# instrumentacion.net
KiCad netlist of a schematic drawn in EAGLE
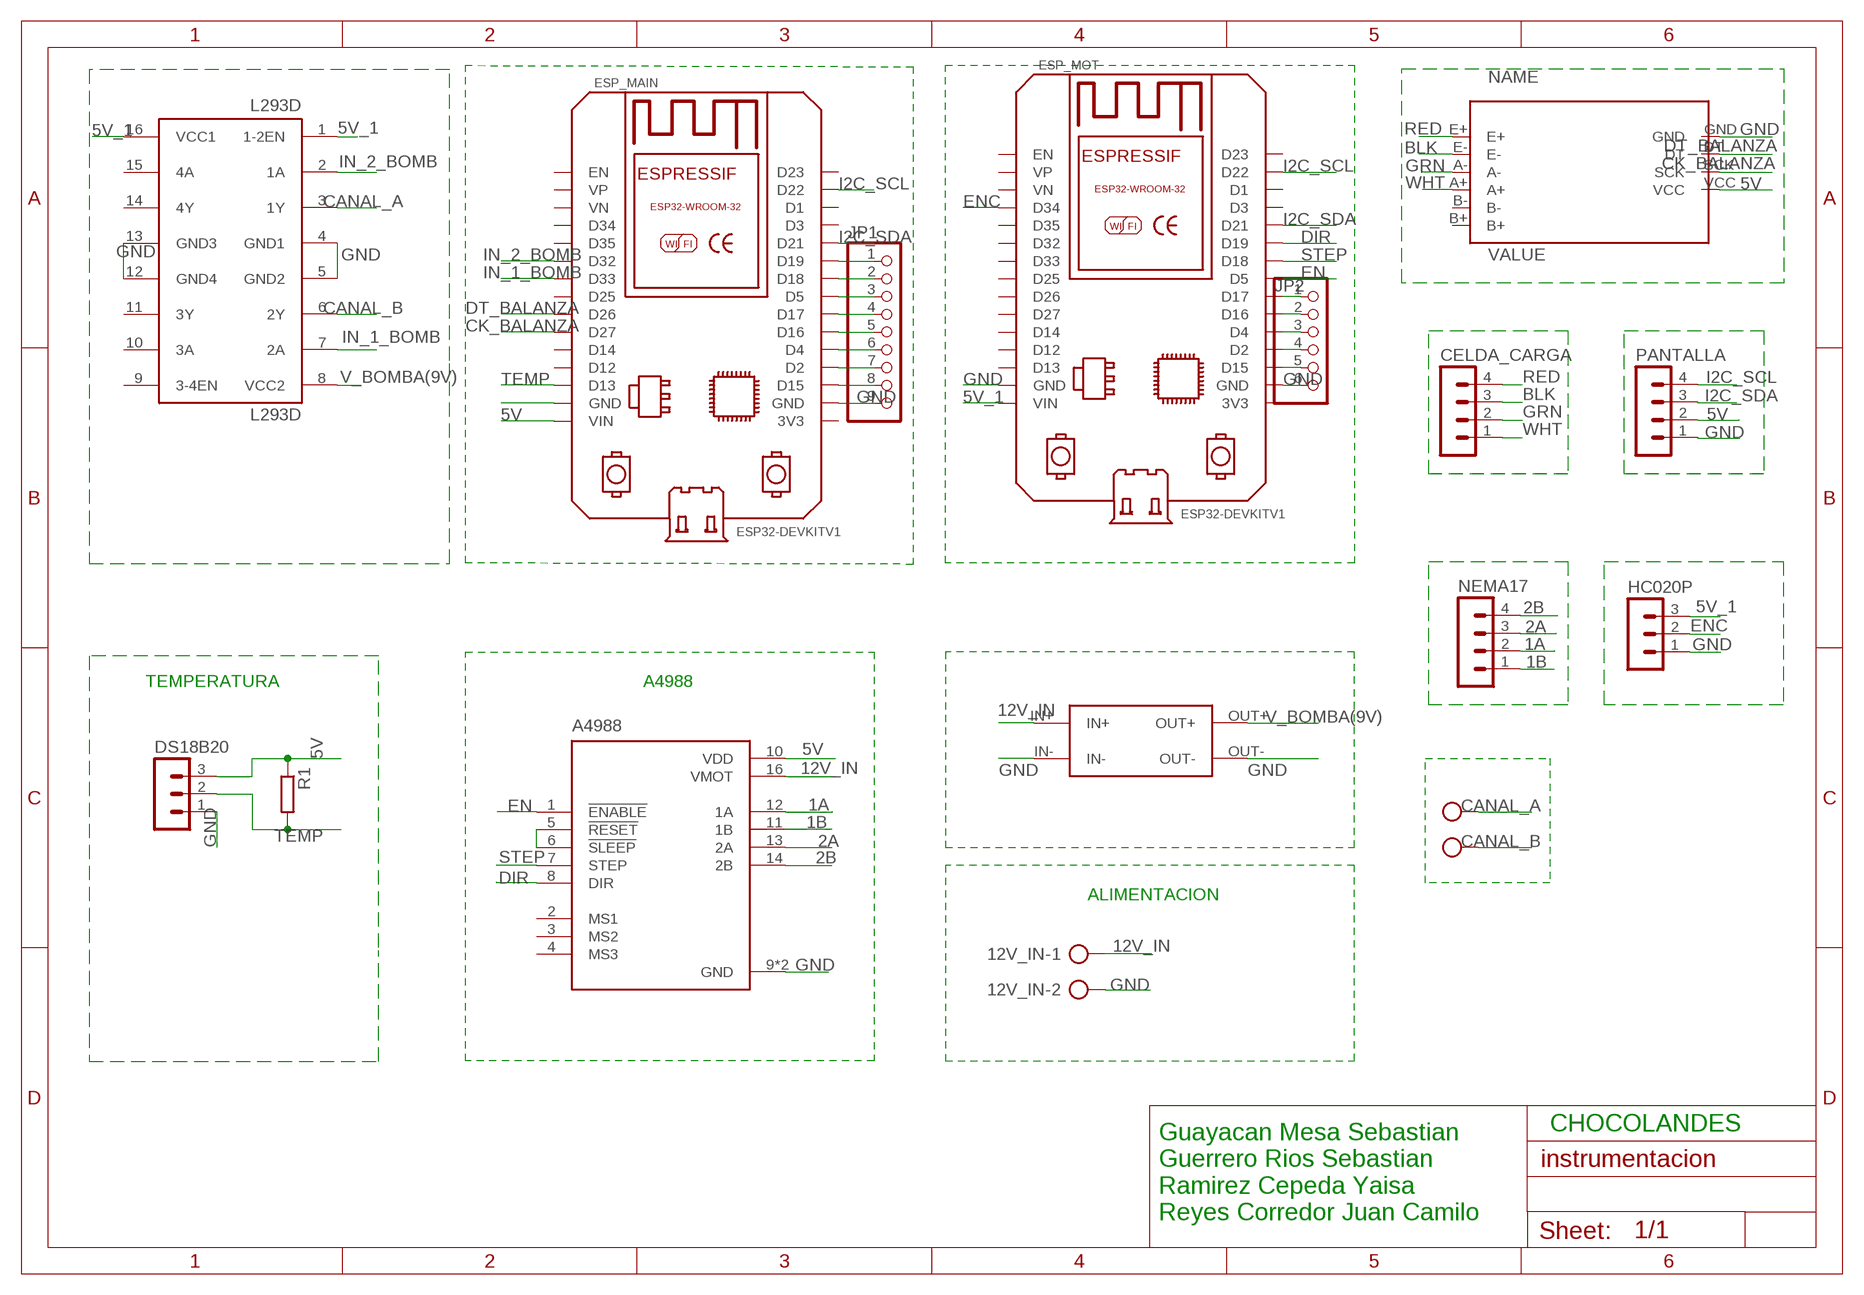
[diagram p0: schematic, sheet 1]

(export (version "E")
  (design (tool "Eeschema 10.0.6"))
  (components
    (comp (ref "12V_IN")
      (value "SMKDSP_1,5/2")
      (footprint "eagle-import:SMKDSP_1,5_2")
      (fields (field (name "MF") "FARNELL") (field (name "MPN") "1733570"))
      (libsource (lib "eagle-import") (part "SMKDSP_1,5/2"))
    )
    (comp (ref "A4988")
      (value "A4988_STEPPER_MOTOR_DRIVER_CARRIER")
      (footprint "eagle-import:MODULE_A4988_STEPPER_MOTOR_DRIVER_CARRIER")
      (fields (field (name "MF") "Pololu") (field (name "MP") "A4988 STEPPER MOTOR DRIVER CARRIER"))
      (libsource (lib "eagle-import") (part "A4988_STEPPER_MOTOR_DRIVER_CARRIER"))
    )
    (comp (ref "BOMBA")
      (value "SMKDSP_1,5/2")
      (footprint "eagle-import:SMKDSP_1,5_2")
      (fields (field (name "MF") "FARNELL") (field (name "MPN") "1733570"))
      (libsource (lib "eagle-import") (part "SMKDSP_1,5/2"))
    )
    (comp (ref "CELDA_CARGA")
      (value "MA04-1")
      (footprint "eagle-import:MA04-1")
      (libsource (lib "eagle-import") (part "MA04-1"))
    )
    (comp (ref "DS18B20")
      (value "MA03-1")
      (footprint "eagle-import:MA03-1")
      (libsource (lib "eagle-import") (part "MA03-1"))
    )
    (comp (ref "ESP_MAIN")
      (value "ESP32DEVKITV1")
      (footprint "eagle-import:ESP32-DEVKITV1")
      (libsource (lib "eagle-import") (part "ESP32DEVKITV1"))
    )
    (comp (ref "ESP_MOT")
      (value "ESP32DEVKITV1")
      (footprint "eagle-import:ESP32-DEVKITV1")
      (libsource (lib "eagle-import") (part "ESP32DEVKITV1"))
    )
    (comp (ref "HC020P")
      (value "MA03-1")
      (footprint "eagle-import:MA03-1")
      (libsource (lib "eagle-import") (part "MA03-1"))
    )
    (comp (ref "HX711")
      (value "HX711A")
      (footprint "eagle-import:HX711")
      (libsource (lib "eagle-import") (part "HX711A"))
    )
    (comp (ref "JP1")
      (value "PINHD-1X9")
      (footprint "eagle-import:1X09")
      (libsource (lib "eagle-import") (part "PINHD-1X9"))
    )
    (comp (ref "JP2")
      (value "PINHD-1X6")
      (footprint "eagle-import:1X06")
      (libsource (lib "eagle-import") (part "PINHD-1X6"))
    )
    (comp (ref "L293D")
      (value "L293D")
      (footprint "eagle-import:DIL16")
      (libsource (lib "eagle-import") (part "L293D"))
    )
    (comp (ref "NEMA17")
      (value "MA04-1")
      (footprint "eagle-import:MA04-1")
      (libsource (lib "eagle-import") (part "MA04-1"))
    )
    (comp (ref "PANTALLA")
      (value "MA04-1")
      (footprint "eagle-import:MA04-1")
      (libsource (lib "eagle-import") (part "MA04-1"))
    )
    (comp (ref "R1")
      (value "R-EU_0204/7")
      (footprint "eagle-import:0204_7")
      (libsource (lib "eagle-import") (part "R-EU_0204/7"))
    )
    (comp (ref "U$1")
      (value "LM2596_3A")
      (footprint "eagle-import:LM259_PADS")
      (libsource (lib "eagle-import") (part "LM2596_3A"))
    )
  )
  (nets
    (net (code "1") (name "/1A") (class "Default")
      (node (ref "A4988") (pin "12") (pinfunction "1A_12") (pintype "output"))
      (node (ref "NEMA17") (pin "2") (pinfunction "2_2") (pintype "passive"))
    )
    (net (code "2") (name "/1B") (class "Default")
      (node (ref "A4988") (pin "11") (pinfunction "1B_11") (pintype "output"))
      (node (ref "NEMA17") (pin "1") (pinfunction "1_1") (pintype "passive"))
    )
    (net (code "3") (name "/2A") (class "Default")
      (node (ref "A4988") (pin "13") (pinfunction "2A_13") (pintype "output"))
      (node (ref "NEMA17") (pin "3") (pinfunction "3_3") (pintype "passive"))
    )
    (net (code "4") (name "/2B") (class "Default")
      (node (ref "A4988") (pin "14") (pinfunction "2B_14") (pintype "output"))
      (node (ref "NEMA17") (pin "4") (pinfunction "4_4") (pintype "passive"))
    )
    (net (code "5") (name "/5V") (class "Default")
      (node (ref "A4988") (pin "10") (pinfunction "VDD_10") (pintype "power_in"))
      (node (ref "DS18B20") (pin "3") (pinfunction "3_3") (pintype "passive"))
      (node (ref "ESP_MAIN") (pin "VIN") (pinfunction "VIN_VIN") (pintype "bidirectional"))
      (node (ref "HX711") (pin "VCC") (pinfunction "VCC_VCC") (pintype "bidirectional"))
      (node (ref "PANTALLA") (pin "2") (pinfunction "2_2") (pintype "passive"))
      (node (ref "R1") (pin "1") (pinfunction "1_1") (pintype "passive"))
    )
    (net (code "6") (name "/5V_1") (class "Default")
      (node (ref "ESP_MOT") (pin "VIN") (pinfunction "VIN_VIN") (pintype "bidirectional"))
      (node (ref "HC020P") (pin "3") (pinfunction "3_3") (pintype "passive"))
      (node (ref "L293D") (pin "1") (pinfunction "1-2EN_1") (pintype "input"))
      (node (ref "L293D") (pin "16") (pinfunction "VCC1_16") (pintype "power_in"))
    )
    (net (code "7") (name "/12V_IN") (class "Default")
      (node (ref "12V_IN") (pin "1") (pinfunction "KL_1") (pintype "passive"))
      (node (ref "A4988") (pin "16") (pinfunction "VMOT_16") (pintype "power_in"))
      (node (ref "U$1") (pin "IN+") (pinfunction "IN+_IN+") (pintype "bidirectional"))
    )
    (net (code "8") (name "/BLK") (class "Default")
      (node (ref "CELDA_CARGA") (pin "3") (pinfunction "3_3") (pintype "passive"))
      (node (ref "HX711") (pin "E-") (pinfunction "E-_E-") (pintype "bidirectional"))
    )
    (net (code "9") (name "/CANAL_A") (class "Default")
      (node (ref "BOMBA") (pin "1") (pinfunction "KL_1") (pintype "passive"))
      (node (ref "L293D") (pin "3") (pinfunction "1Y_3") (pintype "output"))
    )
    (net (code "10") (name "/CANAL_B") (class "Default")
      (node (ref "BOMBA") (pin "2") (pinfunction "KL_2") (pintype "passive"))
      (node (ref "L293D") (pin "6") (pinfunction "2Y_6") (pintype "output"))
    )
    (net (code "11") (name "/CK_BALANZA") (class "Default")
      (node (ref "ESP_MAIN") (pin "D27") (pinfunction "D27_D27") (pintype "bidirectional"))
      (node (ref "HX711") (pin "SCK") (pinfunction "SCK_SCK") (pintype "bidirectional"))
    )
    (net (code "12") (name "/DIR") (class "Default")
      (node (ref "A4988") (pin "8") (pinfunction "DIR_8") (pintype "input"))
      (node (ref "ESP_MOT") (pin "D19") (pinfunction "D19_D19") (pintype "bidirectional"))
    )
    (net (code "13") (name "/DT_BALANZA") (class "Default")
      (node (ref "ESP_MAIN") (pin "D26") (pinfunction "D26_D26") (pintype "bidirectional"))
      (node (ref "HX711") (pin "DT") (pinfunction "DT_DT") (pintype "bidirectional"))
    )
    (net (code "14") (name "/EN") (class "Default")
      (node (ref "A4988") (pin "1") (pinfunction "~{ENABLE}_1") (pintype "input"))
      (node (ref "ESP_MOT") (pin "D5") (pinfunction "D5_D5") (pintype "bidirectional"))
    )
    (net (code "15") (name "/ENC") (class "Default")
      (node (ref "ESP_MOT") (pin "D34") (pinfunction "D34_D34") (pintype "bidirectional"))
      (node (ref "HC020P") (pin "2") (pinfunction "2_2") (pintype "passive"))
    )
    (net (code "16") (name "/GND") (class "Default")
      (node (ref "12V_IN") (pin "2") (pinfunction "KL_2") (pintype "passive"))
      (node (ref "A4988") (pin "15") (pinfunction "GND_15") (pintype "power_in"))
      (node (ref "A4988") (pin "9") (pinfunction "GND_9") (pintype "power_in"))
      (node (ref "DS18B20") (pin "1") (pinfunction "1_1") (pintype "passive"))
      (node (ref "ESP_MAIN") (pin "GND") (pinfunction "GND_GND") (pintype "bidirectional"))
      (node (ref "ESP_MAIN") (pin "GND@1") (pinfunction "GND_GND@1") (pintype "bidirectional"))
      (node (ref "ESP_MOT") (pin "GND") (pinfunction "GND_GND") (pintype "bidirectional"))
      (node (ref "ESP_MOT") (pin "GND@1") (pinfunction "GND_GND@1") (pintype "bidirectional"))
      (node (ref "HC020P") (pin "1") (pinfunction "1_1") (pintype "passive"))
      (node (ref "HX711") (pin "GND") (pinfunction "GND_GND") (pintype "bidirectional"))
      (node (ref "JP1") (pin "9") (pinfunction "9_9") (pintype "passive"))
      (node (ref "JP2") (pin "6") (pinfunction "6_6") (pintype "passive"))
      (node (ref "L293D") (pin "12") (pinfunction "GND4_12") (pintype "power_in"))
      (node (ref "L293D") (pin "13") (pinfunction "GND3_13") (pintype "power_in"))
      (node (ref "L293D") (pin "4") (pinfunction "GND1_4") (pintype "power_in"))
      (node (ref "L293D") (pin "5") (pinfunction "GND2_5") (pintype "power_in"))
      (node (ref "PANTALLA") (pin "1") (pinfunction "1_1") (pintype "passive"))
      (node (ref "U$1") (pin "IN-") (pinfunction "IN-_IN-") (pintype "bidirectional"))
      (node (ref "U$1") (pin "OUT-") (pinfunction "OUT-_OUT-") (pintype "bidirectional"))
    )
    (net (code "17") (name "/GRN") (class "Default")
      (node (ref "CELDA_CARGA") (pin "2") (pinfunction "2_2") (pintype "passive"))
      (node (ref "HX711") (pin "A-") (pinfunction "A-_A-") (pintype "bidirectional"))
    )
    (net (code "18") (name "/I2C_SCL") (class "Default")
      (node (ref "ESP_MAIN") (pin "D22") (pinfunction "D22_D22") (pintype "bidirectional"))
      (node (ref "ESP_MOT") (pin "D22") (pinfunction "D22_D22") (pintype "bidirectional"))
      (node (ref "PANTALLA") (pin "4") (pinfunction "4_4") (pintype "passive"))
    )
    (net (code "19") (name "/I2C_SDA") (class "Default")
      (node (ref "ESP_MAIN") (pin "D21") (pinfunction "D21_D21") (pintype "bidirectional"))
      (node (ref "ESP_MOT") (pin "D21") (pinfunction "D21_D21") (pintype "bidirectional"))
      (node (ref "PANTALLA") (pin "3") (pinfunction "3_3") (pintype "passive"))
    )
    (net (code "20") (name "/IN_1_BOMB") (class "Default")
      (node (ref "ESP_MAIN") (pin "D33") (pinfunction "D33_D33") (pintype "bidirectional"))
      (node (ref "L293D") (pin "7") (pinfunction "2A_7") (pintype "input"))
    )
    (net (code "21") (name "/IN_2_BOMB") (class "Default")
      (node (ref "ESP_MAIN") (pin "D32") (pinfunction "D32_D32") (pintype "bidirectional"))
      (node (ref "L293D") (pin "2") (pinfunction "1A_2") (pintype "input"))
    )
    (net (code "22") (name "/RED") (class "Default")
      (node (ref "CELDA_CARGA") (pin "4") (pinfunction "4_4") (pintype "passive"))
      (node (ref "HX711") (pin "E+") (pinfunction "E+_E+") (pintype "bidirectional"))
    )
    (net (code "23") (name "/STEP") (class "Default")
      (node (ref "A4988") (pin "7") (pinfunction "STEP_7") (pintype "input"))
      (node (ref "ESP_MOT") (pin "D18") (pinfunction "D18_D18") (pintype "bidirectional"))
    )
    (net (code "24") (name "/TEMP") (class "Default")
      (node (ref "DS18B20") (pin "2") (pinfunction "2_2") (pintype "passive"))
      (node (ref "ESP_MAIN") (pin "D13") (pinfunction "D13_D13") (pintype "bidirectional"))
      (node (ref "R1") (pin "2") (pinfunction "2_2") (pintype "passive"))
    )
    (net (code "25") (name "/V_BOMBA(9V)") (class "Default")
      (node (ref "L293D") (pin "8") (pinfunction "VCC2_8") (pintype "power_in"))
      (node (ref "U$1") (pin "OUT+") (pinfunction "OUT+_OUT+") (pintype "bidirectional"))
    )
    (net (code "26") (name "/WHT") (class "Default")
      (node (ref "CELDA_CARGA") (pin "1") (pinfunction "1_1") (pintype "passive"))
      (node (ref "HX711") (pin "A+") (pinfunction "A+_A+") (pintype "bidirectional"))
    )
    (net (code "27") (name "Net-(A4988-~{RESET})") (class "Default")
      (node (ref "A4988") (pin "5") (pinfunction "~{RESET}_5") (pintype "input"))
      (node (ref "A4988") (pin "6") (pinfunction "~{SLEEP}_6") (pintype "input"))
    )
    (net (code "28") (name "Net-(ESP_MAIN-PadD2)") (class "Default")
      (node (ref "ESP_MAIN") (pin "D2") (pinfunction "D2_D2") (pintype "bidirectional"))
      (node (ref "JP1") (pin "7") (pinfunction "7_7") (pintype "passive"))
    )
    (net (code "29") (name "Net-(ESP_MAIN-PadD4)") (class "Default")
      (node (ref "ESP_MAIN") (pin "D4") (pinfunction "D4_D4") (pintype "bidirectional"))
      (node (ref "JP1") (pin "6") (pinfunction "6_6") (pintype "passive"))
    )
    (net (code "30") (name "Net-(ESP_MAIN-PadD5)") (class "Default")
      (node (ref "ESP_MAIN") (pin "D5") (pinfunction "D5_D5") (pintype "bidirectional"))
      (node (ref "JP1") (pin "3") (pinfunction "3_3") (pintype "passive"))
    )
    (net (code "31") (name "Net-(ESP_MAIN-PadD15)") (class "Default")
      (node (ref "ESP_MAIN") (pin "D15") (pinfunction "D15_D15") (pintype "bidirectional"))
      (node (ref "JP1") (pin "8") (pinfunction "8_8") (pintype "passive"))
    )
    (net (code "32") (name "Net-(ESP_MAIN-PadD16)") (class "Default")
      (node (ref "ESP_MAIN") (pin "D16") (pinfunction "D16_D16") (pintype "bidirectional"))
      (node (ref "JP1") (pin "5") (pinfunction "5_5") (pintype "passive"))
    )
    (net (code "33") (name "Net-(ESP_MAIN-PadD17)") (class "Default")
      (node (ref "ESP_MAIN") (pin "D17") (pinfunction "D17_D17") (pintype "bidirectional"))
      (node (ref "JP1") (pin "4") (pinfunction "4_4") (pintype "passive"))
    )
    (net (code "34") (name "Net-(ESP_MAIN-PadD18)") (class "Default")
      (node (ref "ESP_MAIN") (pin "D18") (pinfunction "D18_D18") (pintype "bidirectional"))
      (node (ref "JP1") (pin "2") (pinfunction "2_2") (pintype "passive"))
    )
    (net (code "35") (name "Net-(ESP_MAIN-PadD19)") (class "Default")
      (node (ref "ESP_MAIN") (pin "D19") (pinfunction "D19_D19") (pintype "bidirectional"))
      (node (ref "JP1") (pin "1") (pinfunction "1_1") (pintype "passive"))
    )
    (net (code "36") (name "Net-(ESP_MOT-PadD2)") (class "Default")
      (node (ref "ESP_MOT") (pin "D2") (pinfunction "D2_D2") (pintype "bidirectional"))
      (node (ref "JP2") (pin "4") (pinfunction "4_4") (pintype "passive"))
    )
    (net (code "37") (name "Net-(ESP_MOT-PadD4)") (class "Default")
      (node (ref "ESP_MOT") (pin "D4") (pinfunction "D4_D4") (pintype "bidirectional"))
      (node (ref "JP2") (pin "3") (pinfunction "3_3") (pintype "passive"))
    )
    (net (code "38") (name "Net-(ESP_MOT-PadD15)") (class "Default")
      (node (ref "ESP_MOT") (pin "D15") (pinfunction "D15_D15") (pintype "bidirectional"))
      (node (ref "JP2") (pin "5") (pinfunction "5_5") (pintype "passive"))
    )
    (net (code "39") (name "Net-(ESP_MOT-PadD16)") (class "Default")
      (node (ref "ESP_MOT") (pin "D16") (pinfunction "D16_D16") (pintype "bidirectional"))
      (node (ref "JP2") (pin "2") (pinfunction "2_2") (pintype "passive"))
    )
    (net (code "40") (name "Net-(ESP_MOT-PadD17)") (class "Default")
      (node (ref "ESP_MOT") (pin "D17") (pinfunction "D17_D17") (pintype "bidirectional"))
      (node (ref "JP2") (pin "1") (pinfunction "1_1") (pintype "passive"))
    )
    (net (code "41") (name "unconnected-(A4988-MS1-Pad2)") (class "Default")
      (node (ref "A4988") (pin "2") (pinfunction "MS1_2") (pintype "input"))
    )
    (net (code "42") (name "unconnected-(A4988-MS2-Pad3)") (class "Default")
      (node (ref "A4988") (pin "3") (pinfunction "MS2_3") (pintype "input"))
    )
    (net (code "43") (name "unconnected-(A4988-MS3-Pad4)") (class "Default")
      (node (ref "A4988") (pin "4") (pinfunction "MS3_4") (pintype "input"))
    )
    (net (code "44") (name "unconnected-(ESP_MAIN-Pad3V3)") (class "Default")
      (node (ref "ESP_MAIN") (pin "3V3") (pinfunction "3V3_3V3") (pintype "bidirectional"))
    )
    (net (code "45") (name "unconnected-(ESP_MAIN-PadD1)") (class "Default")
      (node (ref "ESP_MAIN") (pin "D1") (pinfunction "D1_D1") (pintype "bidirectional"))
    )
    (net (code "46") (name "unconnected-(ESP_MAIN-PadD3)") (class "Default")
      (node (ref "ESP_MAIN") (pin "D3") (pinfunction "D3_D3") (pintype "bidirectional"))
    )
    (net (code "47") (name "unconnected-(ESP_MAIN-PadD12)") (class "Default")
      (node (ref "ESP_MAIN") (pin "D12") (pinfunction "D12_D12") (pintype "bidirectional"))
    )
    (net (code "48") (name "unconnected-(ESP_MAIN-PadD14)") (class "Default")
      (node (ref "ESP_MAIN") (pin "D14") (pinfunction "D14_D14") (pintype "bidirectional"))
    )
    (net (code "49") (name "unconnected-(ESP_MAIN-PadD23)") (class "Default")
      (node (ref "ESP_MAIN") (pin "D23") (pinfunction "D23_D23") (pintype "bidirectional"))
    )
    (net (code "50") (name "unconnected-(ESP_MAIN-PadD25)") (class "Default")
      (node (ref "ESP_MAIN") (pin "D25") (pinfunction "D25_D25") (pintype "bidirectional"))
    )
    (net (code "51") (name "unconnected-(ESP_MAIN-PadD34)") (class "Default")
      (node (ref "ESP_MAIN") (pin "D34") (pinfunction "D34_D34") (pintype "bidirectional"))
    )
    (net (code "52") (name "unconnected-(ESP_MAIN-PadD35)") (class "Default")
      (node (ref "ESP_MAIN") (pin "D35") (pinfunction "D35_D35") (pintype "bidirectional"))
    )
    (net (code "53") (name "unconnected-(ESP_MAIN-PadEN)") (class "Default")
      (node (ref "ESP_MAIN") (pin "EN") (pinfunction "EN_EN") (pintype "bidirectional"))
    )
    (net (code "54") (name "unconnected-(ESP_MAIN-PadVN)") (class "Default")
      (node (ref "ESP_MAIN") (pin "VN") (pinfunction "VN_VN") (pintype "bidirectional"))
    )
    (net (code "55") (name "unconnected-(ESP_MAIN-PadVP)") (class "Default")
      (node (ref "ESP_MAIN") (pin "VP") (pinfunction "VP_VP") (pintype "bidirectional"))
    )
    (net (code "56") (name "unconnected-(ESP_MOT-Pad3V3)") (class "Default")
      (node (ref "ESP_MOT") (pin "3V3") (pinfunction "3V3_3V3") (pintype "bidirectional"))
    )
    (net (code "57") (name "unconnected-(ESP_MOT-PadD1)") (class "Default")
      (node (ref "ESP_MOT") (pin "D1") (pinfunction "D1_D1") (pintype "bidirectional"))
    )
    (net (code "58") (name "unconnected-(ESP_MOT-PadD3)") (class "Default")
      (node (ref "ESP_MOT") (pin "D3") (pinfunction "D3_D3") (pintype "bidirectional"))
    )
    (net (code "59") (name "unconnected-(ESP_MOT-PadD12)") (class "Default")
      (node (ref "ESP_MOT") (pin "D12") (pinfunction "D12_D12") (pintype "bidirectional"))
    )
    (net (code "60") (name "unconnected-(ESP_MOT-PadD13)") (class "Default")
      (node (ref "ESP_MOT") (pin "D13") (pinfunction "D13_D13") (pintype "bidirectional"))
    )
    (net (code "61") (name "unconnected-(ESP_MOT-PadD14)") (class "Default")
      (node (ref "ESP_MOT") (pin "D14") (pinfunction "D14_D14") (pintype "bidirectional"))
    )
    (net (code "62") (name "unconnected-(ESP_MOT-PadD23)") (class "Default")
      (node (ref "ESP_MOT") (pin "D23") (pinfunction "D23_D23") (pintype "bidirectional"))
    )
    (net (code "63") (name "unconnected-(ESP_MOT-PadD25)") (class "Default")
      (node (ref "ESP_MOT") (pin "D25") (pinfunction "D25_D25") (pintype "bidirectional"))
    )
    (net (code "64") (name "unconnected-(ESP_MOT-PadD26)") (class "Default")
      (node (ref "ESP_MOT") (pin "D26") (pinfunction "D26_D26") (pintype "bidirectional"))
    )
    (net (code "65") (name "unconnected-(ESP_MOT-PadD27)") (class "Default")
      (node (ref "ESP_MOT") (pin "D27") (pinfunction "D27_D27") (pintype "bidirectional"))
    )
    (net (code "66") (name "unconnected-(ESP_MOT-PadD32)") (class "Default")
      (node (ref "ESP_MOT") (pin "D32") (pinfunction "D32_D32") (pintype "bidirectional"))
    )
    (net (code "67") (name "unconnected-(ESP_MOT-PadD33)") (class "Default")
      (node (ref "ESP_MOT") (pin "D33") (pinfunction "D33_D33") (pintype "bidirectional"))
    )
    (net (code "68") (name "unconnected-(ESP_MOT-PadD35)") (class "Default")
      (node (ref "ESP_MOT") (pin "D35") (pinfunction "D35_D35") (pintype "bidirectional"))
    )
    (net (code "69") (name "unconnected-(ESP_MOT-PadEN)") (class "Default")
      (node (ref "ESP_MOT") (pin "EN") (pinfunction "EN_EN") (pintype "bidirectional"))
    )
    (net (code "70") (name "unconnected-(ESP_MOT-PadVN)") (class "Default")
      (node (ref "ESP_MOT") (pin "VN") (pinfunction "VN_VN") (pintype "bidirectional"))
    )
    (net (code "71") (name "unconnected-(ESP_MOT-PadVP)") (class "Default")
      (node (ref "ESP_MOT") (pin "VP") (pinfunction "VP_VP") (pintype "bidirectional"))
    )
    (net (code "72") (name "unconnected-(HX711-PadB+)") (class "Default")
      (node (ref "HX711") (pin "B+") (pinfunction "B+_B+") (pintype "bidirectional"))
    )
    (net (code "73") (name "unconnected-(HX711-PadB-)") (class "Default")
      (node (ref "HX711") (pin "B-") (pinfunction "B-_B-") (pintype "bidirectional"))
    )
    (net (code "74") (name "unconnected-(L293D-3-4EN-Pad9)") (class "Default")
      (node (ref "L293D") (pin "9") (pinfunction "3-4EN_9") (pintype "input"))
    )
    (net (code "75") (name "unconnected-(L293D-3A-Pad10)") (class "Default")
      (node (ref "L293D") (pin "10") (pinfunction "3A_10") (pintype "input"))
    )
    (net (code "76") (name "unconnected-(L293D-3Y-Pad11)") (class "Default")
      (node (ref "L293D") (pin "11") (pinfunction "3Y_11") (pintype "output"))
    )
    (net (code "77") (name "unconnected-(L293D-4A-Pad15)") (class "Default")
      (node (ref "L293D") (pin "15") (pinfunction "4A_15") (pintype "input"))
    )
    (net (code "78") (name "unconnected-(L293D-4Y-Pad14)") (class "Default")
      (node (ref "L293D") (pin "14") (pinfunction "4Y_14") (pintype "output"))
    )
  )
)
